# Function_gen_schem.net
KiCad netlist of a schematic drawn in Altium Designer
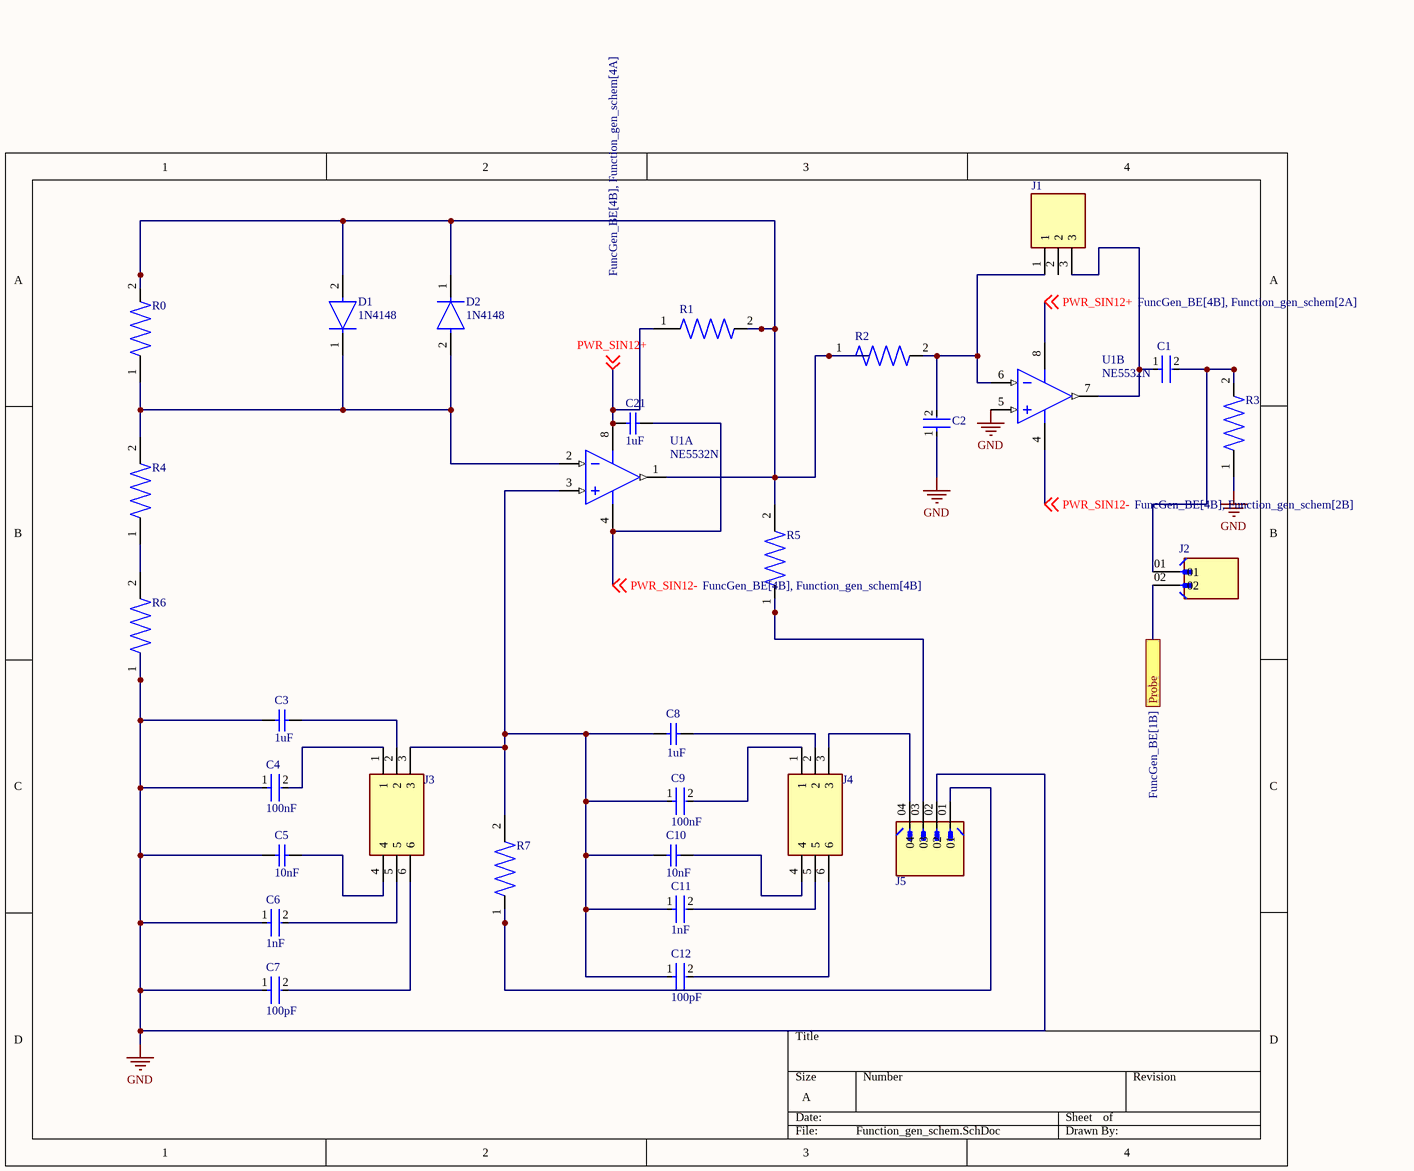
[diagram p0: Function_gen_schem.SchDoc]

(export (version "E")
  (design (tool "Eeschema 10.0.6"))
  (components
    (comp (ref "C1")
      (value "SR205C104KAR")
      (footprint "FP-SR20-MFG")
      (description "CAP CER 0.1UF 50V X7R RADIAL")
      (fields (field (name "VOLTAGE") "50V") (field (name "TOLERANCE") "10%"))
      (libsource (lib "Altium Content Vault") (part "11868f565c42a9108669ba33697ecf6"))
    )
    (comp (ref "C2")
      (value "RCE5C1H271J0K1H03B")
      (footprint "FP-RCE0K1-MFG")
      (description "Cap Ceramic 270pF 50V C0G ±5% Radial 5mm +125°C Automotive Bulk")
      (fields (field (name "TOLERANCE") "5%"))
      (libsource (lib "Altium Content Vault") (part "b4654b650e69147ec39a6b967a45e02"))
    )
    (comp (ref "C3")
      (value "1uF")
      (footprint "KEMT-C330C105M5U5TA")
      (description "Ceramic Capacitor, 1 uF, +/- 20%, 50 V, -10 to 85 degC, 2-Pin THD, RoHS, Bulk")
      (fields (field (name "TOLERANCE") "±20%") (field (name "MANUFACTURER") "Kemet"))
      (libsource (lib "Altium Content Vault") (part "CAP-NP-2"))
    )
    (comp (ref "C4")
      (value "100nF")
      (footprint "FP-C322C104K5R5TA-MFG")
      (description "CAP CER 0.1UF 50V X7R RADIAL")
      (fields (field (name "TOLERANCE") "10%") (field (name "VOLTAGE") "50V"))
      (libsource (lib "Altium Content Vault") (part "b4654b650e69147ec39a6b967a45e02"))
    )
    (comp (ref "C5")
      (value "10nF")
      (footprint "KEMT-C315-THT-2")
      (description "Capacitor, Ceramic, 0.01 uF, +/- 10%, 100 V, X7R, -55 to 125 degC, 2-Pin THD, RoHS, Bulk")
      (libsource (lib "Altium Content Vault") (part "CAP-NP-2"))
    )
    (comp (ref "C6")
      (value "1nF")
      (footprint "FP-DE6_D7_T7_F7_5_d0_6-0-MFG")
      (description "CAP CER 1000PF 300VAC RADIAL")
      (fields (field (name "TOLERANCE") "20%"))
      (libsource (lib "Altium Content Vault") (part "7bc8f122f62ff4f5a687363419e79e3"))
    )
    (comp (ref "C7")
      (value "100pF")
      (footprint "FP-RCE0K1-MFG")
      (description "Cap Ceramic 100pF 50V C0G ±5% Radial 5mm +125°C Automotive Bulk")
      (fields (field (name "TOLERANCE") "5%"))
      (libsource (lib "Altium Content Vault") (part "b4654b650e69147ec39a6b967a45e02"))
    )
    (comp (ref "C8")
      (value "1uF")
      (footprint "KEMT-C330C105M5U5TA")
      (description "Ceramic Capacitor, 1 uF, +/- 20%, 50 V, -10 to 85 degC, 2-Pin THD, RoHS, Bulk")
      (fields (field (name "TOLERANCE") "±20%") (field (name "MANUFACTURER") "Kemet"))
      (libsource (lib "Altium Content Vault") (part "CAP-NP-2"))
    )
    (comp (ref "C9")
      (value "100nF")
      (footprint "FP-C322C104K5R5TA-MFG")
      (description "CAP CER 0.1UF 50V X7R RADIAL")
      (fields (field (name "TOLERANCE") "10%") (field (name "VOLTAGE") "50V"))
      (libsource (lib "Altium Content Vault") (part "b4654b650e69147ec39a6b967a45e02"))
    )
    (comp (ref "C10")
      (value "10nF")
      (footprint "KEMT-C315-THT-2")
      (description "Capacitor, Ceramic, 0.01 uF, +/- 10%, 100 V, X7R, -55 to 125 degC, 2-Pin THD, RoHS, Bulk")
      (libsource (lib "Altium Content Vault") (part "CAP-NP-2"))
    )
    (comp (ref "C11")
      (value "1nF")
      (footprint "FP-DE6_D7_T7_F7_5_d0_6-0-MFG")
      (description "CAP CER 1000PF 300VAC RADIAL")
      (fields (field (name "TOLERANCE") "20%"))
      (libsource (lib "Altium Content Vault") (part "7bc8f122f62ff4f5a687363419e79e3"))
    )
    (comp (ref "C12")
      (value "100pF")
      (footprint "FP-RCE0K1-MFG")
      (description "Cap Ceramic 100pF 50V C0G ±5% Radial 5mm +125°C Automotive Bulk")
      (fields (field (name "TOLERANCE") "5%"))
      (libsource (lib "Altium Content Vault") (part "b4654b650e69147ec39a6b967a45e02"))
    )
    (comp (ref "C21")
      (value "1uF")
      (footprint "KEMT-C330C105M5U5TA")
      (description "Ceramic Capacitor, 1 uF, +/- 20%, 50 V, -10 to 85 degC, 2-Pin THD, RoHS, Bulk")
      (fields (field (name "TOLERANCE") "±20%") (field (name "MANUFACTURER") "Kemet"))
      (libsource (lib "Altium Content Vault") (part "CAP-NP-2"))
    )
    (comp (ref "D1")
      (value "1N4148")
      (footprint "FP-017AG-MFG")
      (description "DIODE GEN PURP 100V 200MA DO35")
      (fields (field (name "VOLTAGE") "100V"))
      (libsource (lib "Altium Content Vault") (part "d7152d700b627762746794eb795d46e"))
    )
    (comp (ref "D2")
      (value "1N4148")
      (footprint "FP-017AG-MFG")
      (description "DIODE GEN PURP 100V 200MA DO35")
      (fields (field (name "VOLTAGE") "100V"))
      (libsource (lib "Altium Content Vault") (part "d7152d700b627762746794eb795d46e"))
    )
    (comp (ref "J1")
      (value "3-644456-3")
      (footprint "TE_3-644456-3")
      (description "MTA-100 3 Position Through-Hole Single Row Straight Wire to Board Header")
      (fields (field (name "MF") "TE Connectivity"))
      (libsource (lib "3-644456-3") (part "3-644456-3"))
    )
    (comp (ref "J2")
      (value "861400021YO2LF")
      (footprint "AMPHENOL_861400021YO2LF")
      (description "Board to Board connector, Unshrouded Header, Through Hole, Single Row, 2 Position, Vertical.")
      (fields (field (name "MF") "Amphenol ICC (FCI)"))
      (libsource (lib "861400021YO2LF") (part "861400021YO2LF"))
    )
    (comp (ref "J3")
      (value "4-103327-6")
      (footprint "TE_4-103327-6")
      (description "6 Position Single Row 2.54 mm Through-Hole Straight AMPMODU Breakaway Header")
      (fields (field (name "MF") "TE Connectivity"))
      (libsource (lib "4-103327-6") (part "4-103327-6"))
    )
    (comp (ref "J4")
      (value "4-103327-6")
      (footprint "TE_4-103327-6")
      (description "6 Position Single Row 2.54 mm Through-Hole Straight AMPMODU Breakaway Header")
      (fields (field (name "MF") "TE Connectivity"))
      (libsource (lib "4-103327-6") (part "4-103327-6"))
    )
    (comp (ref "J5")
      (value "77311-102S04LF")
      (footprint "AMPHENOL_77311-102S04LF")
      (fields (field (name "MF") "Amphenol ICC (FCI)"))
      (libsource (lib "77311-102S04LF") (part "77311-102S04LF"))
    )
    (comp (ref "R0")
      (value "3-1623927-1")
      (footprint "RESAD700W45L350D185")
      (description "1 MOhms Â±5% 0.25W, 1/4W Through Hole Resistor Axial - Carbon Film")
      (fields (field (name "MF") "TE Connectivity"))
      (libsource (lib "3-1623927-1") (part "3-1623927-1"))
    )
    (comp (ref "R1")
      (value "3-1623927-1")
      (footprint "RESAD700W45L350D185")
      (description "1 MOhms Â±5% 0.25W, 1/4W Through Hole Resistor Axial - Carbon Film")
      (fields (field (name "MF") "TE Connectivity"))
      (libsource (lib "3-1623927-1") (part "3-1623927-1"))
    )
    (comp (ref "R2")
      (value "3-1623927-1")
      (footprint "RESAD700W45L350D185")
      (description "1 MOhms Â±5% 0.25W, 1/4W Through Hole Resistor Axial - Carbon Film")
      (fields (field (name "MF") "TE Connectivity"))
      (libsource (lib "3-1623927-1") (part "3-1623927-1"))
    )
    (comp (ref "R3")
      (value "3-1623927-1")
      (footprint "RESAD700W45L350D185")
      (description "1 MOhms Â±5% 0.25W, 1/4W Through Hole Resistor Axial - Carbon Film")
      (fields (field (name "MF") "TE Connectivity"))
      (libsource (lib "3-1623927-1") (part "3-1623927-1"))
    )
    (comp (ref "R4")
      (value "3-1623927-1")
      (footprint "RESAD700W45L350D185")
      (description "1 MOhms Â±5% 0.25W, 1/4W Through Hole Resistor Axial - Carbon Film")
      (fields (field (name "MF") "TE Connectivity"))
      (libsource (lib "3-1623927-1") (part "3-1623927-1"))
    )
    (comp (ref "R5")
      (value "3-1623927-1")
      (footprint "RESAD700W45L350D185")
      (description "1 MOhms Â±5% 0.25W, 1/4W Through Hole Resistor Axial - Carbon Film")
      (fields (field (name "MF") "TE Connectivity"))
      (libsource (lib "3-1623927-1") (part "3-1623927-1"))
    )
    (comp (ref "R6")
      (value "3-1623927-1")
      (footprint "RESAD700W45L350D185")
      (description "1 MOhms Â±5% 0.25W, 1/4W Through Hole Resistor Axial - Carbon Film")
      (fields (field (name "MF") "TE Connectivity"))
      (libsource (lib "3-1623927-1") (part "3-1623927-1"))
    )
    (comp (ref "R7")
      (value "3-1623927-1")
      (footprint "RESAD700W45L350D185")
      (description "1 MOhms Â±5% 0.25W, 1/4W Through Hole Resistor Axial - Carbon Film")
      (fields (field (name "MF") "TE Connectivity"))
      (libsource (lib "3-1623927-1") (part "3-1623927-1"))
    )
    (comp (ref "U1")
      (value "NE5532N")
      (footprint "ONSC-PDIP-8-626-05")
      (fields (field (name "MANUFACTURER") "On Semiconductor"))
      (libsource (lib "Altium Content Vault") (part "ONSC-NE5532-PDIP-8-626-05"))
    )
  )
  (nets
    (net (code "1") (name "/Probe") (class "Default")
      (node (ref "J2") (pin "02") (pinfunction "02_02") (pintype "passive"))
    )
    (net (code "2") (name "GND") (class "Default")
      (node (ref "C2") (pin "1") (pinfunction "1_1") (pintype "passive"))
      (node (ref "C3") (pin "1") (pinfunction "1_1") (pintype "passive"))
      (node (ref "C4") (pin "1") (pinfunction "1_1") (pintype "passive"))
      (node (ref "C5") (pin "1") (pinfunction "1_1") (pintype "passive"))
      (node (ref "C6") (pin "1") (pinfunction "1_1") (pintype "passive"))
      (node (ref "C7") (pin "1") (pinfunction "1_1") (pintype "passive"))
      (node (ref "J5") (pin "02") (pinfunction "02_02") (pintype "passive"))
      (node (ref "R3") (pin "1") (pinfunction "1_1") (pintype "passive"))
      (node (ref "R6") (pin "1") (pinfunction "1_1") (pintype "passive"))
      (node (ref "U1") (pin "5") (pinfunction "INB+_5") (pintype "input"))
    )
    (net (code "3") (name "Net-(C1-Pad2)") (class "Default")
      (node (ref "C1") (pin "2") (pinfunction "2_2") (pintype "passive"))
      (node (ref "J2") (pin "01") (pinfunction "01_01") (pintype "passive"))
      (node (ref "R3") (pin "2") (pinfunction "2_2") (pintype "passive"))
    )
    (net (code "4") (name "Net-(C3-Pad2)") (class "Default")
      (node (ref "C3") (pin "2") (pinfunction "2_2") (pintype "passive"))
      (node (ref "J3") (pin "2") (pinfunction "2_2") (pintype "passive"))
    )
    (net (code "5") (name "Net-(C4-Pad2)") (class "Default")
      (node (ref "C4") (pin "2") (pinfunction "2_2") (pintype "passive"))
      (node (ref "J3") (pin "1") (pinfunction "1_1") (pintype "passive"))
    )
    (net (code "6") (name "Net-(C5-Pad2)") (class "Default")
      (node (ref "C5") (pin "2") (pinfunction "2_2") (pintype "passive"))
      (node (ref "J3") (pin "4") (pinfunction "4_4") (pintype "passive"))
    )
    (net (code "7") (name "Net-(C6-Pad2)") (class "Default")
      (node (ref "C6") (pin "2") (pinfunction "2_2") (pintype "passive"))
      (node (ref "J3") (pin "5") (pinfunction "5_5") (pintype "passive"))
    )
    (net (code "8") (name "Net-(C7-Pad2)") (class "Default")
      (node (ref "C7") (pin "2") (pinfunction "2_2") (pintype "passive"))
      (node (ref "J3") (pin "6") (pinfunction "6_6") (pintype "passive"))
    )
    (net (code "9") (name "Net-(C8-Pad2)") (class "Default")
      (node (ref "C8") (pin "2") (pinfunction "2_2") (pintype "passive"))
      (node (ref "J4") (pin "2") (pinfunction "2_2") (pintype "passive"))
    )
    (net (code "10") (name "Net-(C9-Pad2)") (class "Default")
      (node (ref "C9") (pin "2") (pinfunction "2_2") (pintype "passive"))
      (node (ref "J4") (pin "1") (pinfunction "1_1") (pintype "passive"))
    )
    (net (code "11") (name "Net-(C10-Pad2)") (class "Default")
      (node (ref "C10") (pin "2") (pinfunction "2_2") (pintype "passive"))
      (node (ref "J4") (pin "4") (pinfunction "4_4") (pintype "passive"))
    )
    (net (code "12") (name "Net-(C11-Pad2)") (class "Default")
      (node (ref "C11") (pin "2") (pinfunction "2_2") (pintype "passive"))
      (node (ref "J4") (pin "5") (pinfunction "5_5") (pintype "passive"))
    )
    (net (code "13") (name "Net-(C12-Pad2)") (class "Default")
      (node (ref "C12") (pin "2") (pinfunction "2_2") (pintype "passive"))
      (node (ref "J4") (pin "6") (pinfunction "6_6") (pintype "passive"))
    )
    (net (code "14") (name "Net-(D1-A)") (class "Default")
      (node (ref "D1") (pin "2") (pinfunction "A_2") (pintype "passive"))
      (node (ref "D2") (pin "1") (pinfunction "C_1") (pintype "passive"))
      (node (ref "R0") (pin "2") (pinfunction "2_2") (pintype "passive"))
      (node (ref "R1") (pin "2") (pinfunction "2_2") (pintype "passive"))
      (node (ref "R2") (pin "1") (pinfunction "1_1") (pintype "passive"))
      (node (ref "R5") (pin "2") (pinfunction "2_2") (pintype "passive"))
      (node (ref "U1") (pin "1") (pinfunction "OUTA_1") (pintype "output"))
    )
    (net (code "15") (name "Net-(D1-C)") (class "Default")
      (node (ref "D1") (pin "1") (pinfunction "C_1") (pintype "passive"))
      (node (ref "D2") (pin "2") (pinfunction "A_2") (pintype "passive"))
      (node (ref "R0") (pin "1") (pinfunction "1_1") (pintype "passive"))
      (node (ref "R4") (pin "2") (pinfunction "2_2") (pintype "passive"))
      (node (ref "U1") (pin "2") (pinfunction "INA-_2") (pintype "input"))
    )
    (net (code "16") (name "Net-(J4-Pad3)") (class "Default")
      (node (ref "J4") (pin "3") (pinfunction "3_3") (pintype "passive"))
      (node (ref "J5") (pin "04") (pinfunction "04_04") (pintype "passive"))
    )
    (net (code "17") (name "Net-(J5-Pad01)") (class "Default")
      (node (ref "J5") (pin "01") (pinfunction "01_01") (pintype "passive"))
      (node (ref "R7") (pin "1") (pinfunction "1_1") (pintype "passive"))
    )
    (net (code "18") (name "Net-(J5-Pad03)") (class "Default")
      (node (ref "J5") (pin "03") (pinfunction "03_03") (pintype "passive"))
      (node (ref "R5") (pin "1") (pinfunction "1_1") (pintype "passive"))
    )
    (net (code "19") (name "Net-(R4-Pad1)") (class "Default")
      (node (ref "R4") (pin "1") (pinfunction "1_1") (pintype "passive"))
      (node (ref "R6") (pin "2") (pinfunction "2_2") (pintype "passive"))
    )
    (net (code "20") (name "Net-(U1A-INA+)") (class "Default")
      (node (ref "C10") (pin "1") (pinfunction "1_1") (pintype "passive"))
      (node (ref "C11") (pin "1") (pinfunction "1_1") (pintype "passive"))
      (node (ref "C12") (pin "1") (pinfunction "1_1") (pintype "passive"))
      (node (ref "C8") (pin "1") (pinfunction "1_1") (pintype "passive"))
      (node (ref "C9") (pin "1") (pinfunction "1_1") (pintype "passive"))
      (node (ref "J3") (pin "3") (pinfunction "3_3") (pintype "passive"))
      (node (ref "R7") (pin "2") (pinfunction "2_2") (pintype "passive"))
      (node (ref "U1") (pin "3") (pinfunction "INA+_3") (pintype "input"))
    )
    (net (code "21") (name "Net-(U1B-INB-)") (class "Default")
      (node (ref "C2") (pin "2") (pinfunction "2_2") (pintype "passive"))
      (node (ref "J1") (pin "1") (pinfunction "1_1") (pintype "passive"))
      (node (ref "R2") (pin "2") (pinfunction "2_2") (pintype "passive"))
      (node (ref "U1") (pin "6") (pinfunction "INB-_6") (pintype "input"))
    )
    (net (code "22") (name "Net-(U1B-OUTB)") (class "Default")
      (node (ref "C1") (pin "1") (pinfunction "1_1") (pintype "passive"))
      (node (ref "J1") (pin "3") (pinfunction "3_3") (pintype "passive"))
      (node (ref "U1") (pin "7") (pinfunction "OUTB_7") (pintype "output"))
    )
    (net (code "23") (name "PWR_SIN12+") (class "Default")
      (node (ref "C21") (pin "1") (pinfunction "1_1") (pintype "passive"))
      (node (ref "R1") (pin "1") (pinfunction "1_1") (pintype "passive"))
      (node (ref "U1") (pin "8") (pinfunction "V+_8") (pintype "power_in"))
    )
    (net (code "24") (name "PWR_SIN12-") (class "Default")
      (node (ref "C21") (pin "2") (pinfunction "2_2") (pintype "passive"))
      (node (ref "U1") (pin "4") (pinfunction "V-_4") (pintype "power_in"))
    )
    (net (code "25") (name "unconnected-(J1-Pad2)") (class "Default")
      (node (ref "J1") (pin "2") (pinfunction "2_2") (pintype "passive"))
    )
  )
)
